# Encoder_Breakout.net
KiCad netlist of a schematic drawn in EAGLE
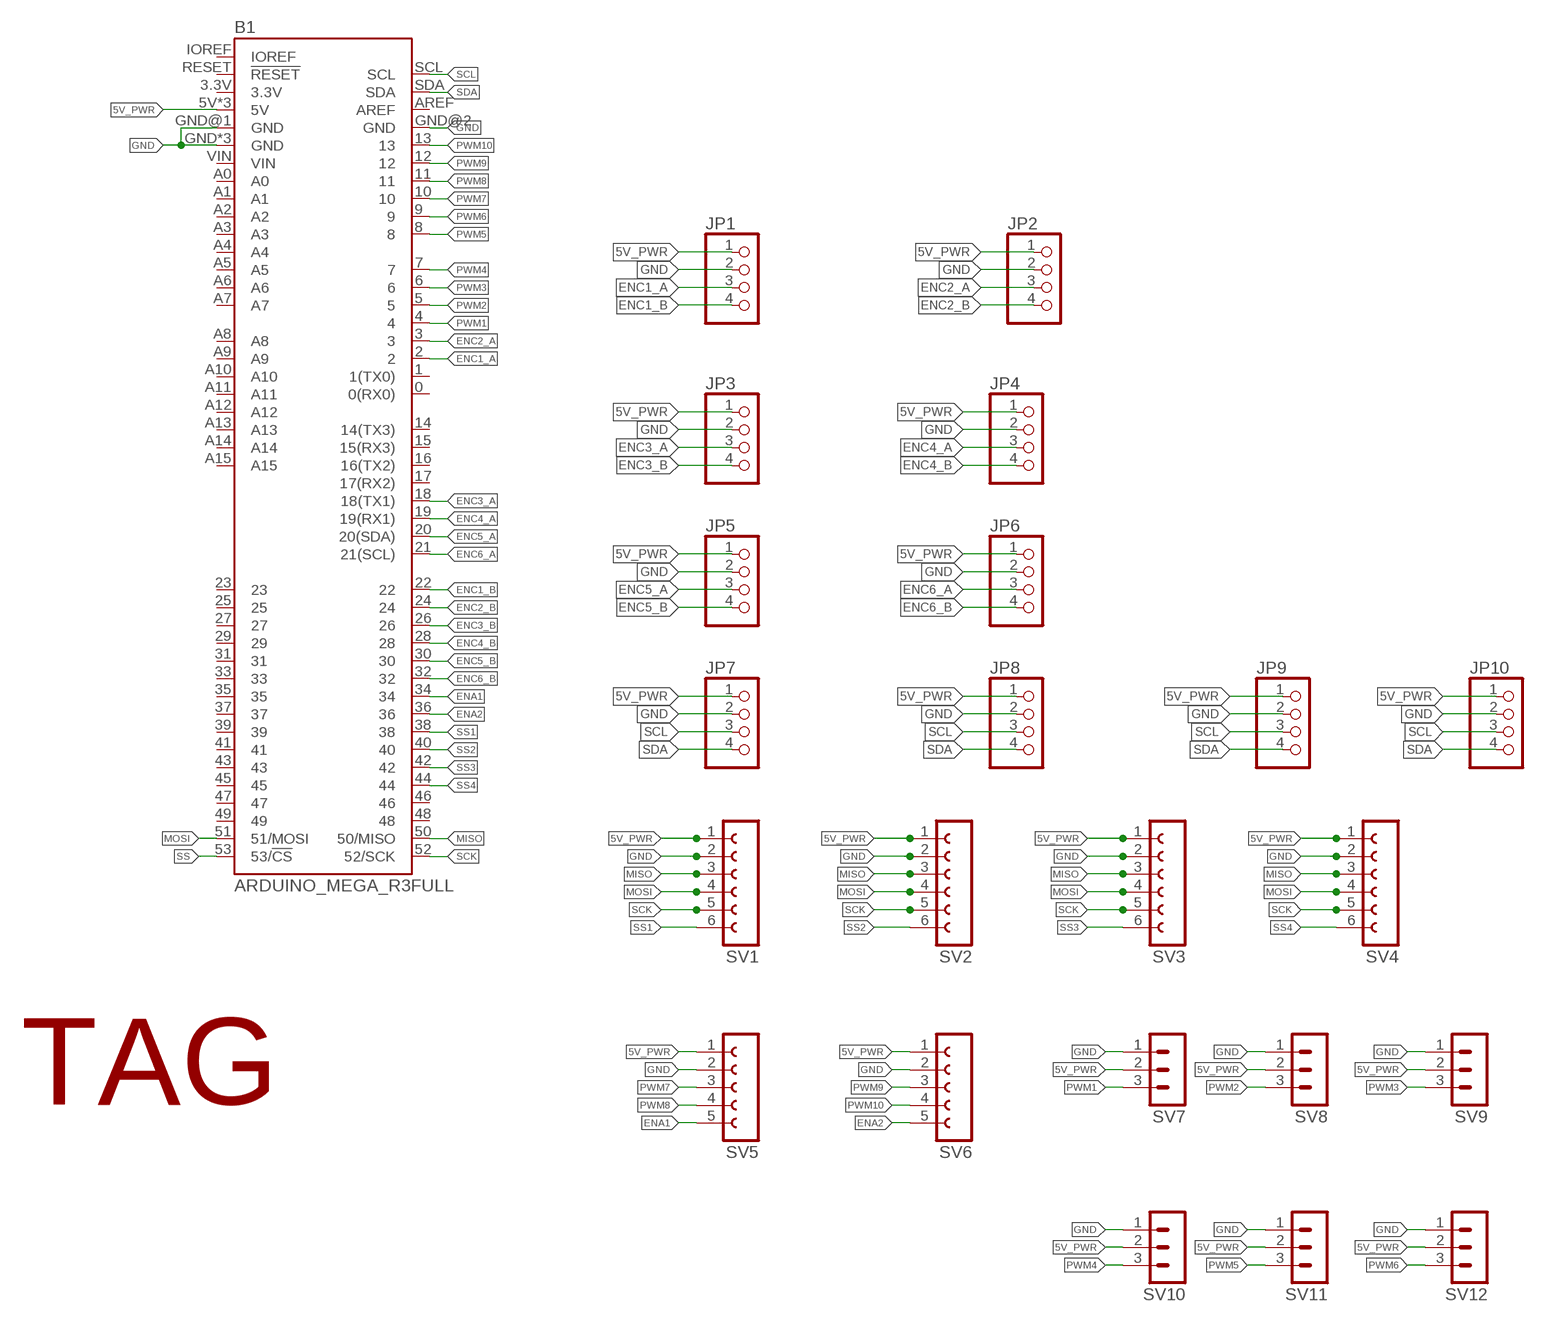
[diagram p0: schematic, sheet 1]

(export (version "E")
  (design (tool "Eeschema 10.0.6"))
  (components
    (comp (ref "B1")
      (value "ARDUINO_MEGA_R3FULL")
      (footprint "eagle-import:ARDUINO_MEGA_NO_SILK")
      (libsource (lib "eagle-import") (part "ARDUINO_MEGA_R3FULL"))
    )
    (comp (ref "JP1")
      (value "PINHD-1X4")
      (footprint "eagle-import:1X04")
      (libsource (lib "eagle-import") (part "PINHD-1X4"))
    )
    (comp (ref "JP2")
      (value "PINHD-1X4")
      (footprint "eagle-import:1X04")
      (libsource (lib "eagle-import") (part "PINHD-1X4"))
    )
    (comp (ref "JP3")
      (value "PINHD-1X4")
      (footprint "eagle-import:1X04")
      (libsource (lib "eagle-import") (part "PINHD-1X4"))
    )
    (comp (ref "JP4")
      (value "PINHD-1X4")
      (footprint "eagle-import:1X04")
      (libsource (lib "eagle-import") (part "PINHD-1X4"))
    )
    (comp (ref "JP5")
      (value "PINHD-1X4")
      (footprint "eagle-import:1X04")
      (libsource (lib "eagle-import") (part "PINHD-1X4"))
    )
    (comp (ref "JP6")
      (value "PINHD-1X4")
      (footprint "eagle-import:1X04")
      (libsource (lib "eagle-import") (part "PINHD-1X4"))
    )
    (comp (ref "JP7")
      (value "PINHD-1X4")
      (footprint "eagle-import:1X04")
      (libsource (lib "eagle-import") (part "PINHD-1X4"))
    )
    (comp (ref "JP8")
      (value "PINHD-1X4")
      (footprint "eagle-import:1X04")
      (libsource (lib "eagle-import") (part "PINHD-1X4"))
    )
    (comp (ref "JP9")
      (value "PINHD-1X4")
      (footprint "eagle-import:1X04")
      (libsource (lib "eagle-import") (part "PINHD-1X4"))
    )
    (comp (ref "JP10")
      (value "PINHD-1X4")
      (footprint "eagle-import:1X04")
      (libsource (lib "eagle-import") (part "PINHD-1X4"))
    )
    (comp (ref "SV1")
      (value "FE06-1")
      (footprint "eagle-import:FE06")
      (libsource (lib "eagle-import") (part "FE06-1"))
    )
    (comp (ref "SV2")
      (value "FE06-1")
      (footprint "eagle-import:FE06")
      (libsource (lib "eagle-import") (part "FE06-1"))
    )
    (comp (ref "SV3")
      (value "FE06-1")
      (footprint "eagle-import:FE06")
      (libsource (lib "eagle-import") (part "FE06-1"))
    )
    (comp (ref "SV4")
      (value "FE06-1")
      (footprint "eagle-import:FE06")
      (libsource (lib "eagle-import") (part "FE06-1"))
    )
    (comp (ref "SV5")
      (value "FE05-1")
      (footprint "eagle-import:FE05-1")
      (libsource (lib "eagle-import") (part "FE05-1"))
    )
    (comp (ref "SV6")
      (value "FE05-1")
      (footprint "eagle-import:FE05-1")
      (libsource (lib "eagle-import") (part "FE05-1"))
    )
    (comp (ref "SV7")
      (value "MA03-1")
      (footprint "eagle-import:MA03-1")
      (libsource (lib "eagle-import") (part "MA03-1"))
    )
    (comp (ref "SV8")
      (value "MA03-1")
      (footprint "eagle-import:MA03-1")
      (libsource (lib "eagle-import") (part "MA03-1"))
    )
    (comp (ref "SV9")
      (value "MA03-1")
      (footprint "eagle-import:MA03-1")
      (libsource (lib "eagle-import") (part "MA03-1"))
    )
    (comp (ref "SV10")
      (value "MA03-1")
      (footprint "eagle-import:MA03-1")
      (libsource (lib "eagle-import") (part "MA03-1"))
    )
    (comp (ref "SV11")
      (value "MA03-1")
      (footprint "eagle-import:MA03-1")
      (libsource (lib "eagle-import") (part "MA03-1"))
    )
    (comp (ref "SV12")
      (value "MA03-1")
      (footprint "eagle-import:MA03-1")
      (libsource (lib "eagle-import") (part "MA03-1"))
    )
    (comp (ref "U$1")
      (value "TAG")
      (footprint "eagle-import:TAG")
      (libsource (lib "eagle-import") (part "TAG"))
    )
  )
  (nets
    (net (code "1") (name "5V_PWR") (class "Default")
      (node (ref "B1") (pin "5V") (pinfunction "5V_5V") (pintype "bidirectional"))
      (node (ref "B1") (pin "5V@1") (pinfunction "5V_5V@1") (pintype "bidirectional"))
      (node (ref "B1") (pin "5V@2") (pinfunction "5V_5V@2") (pintype "bidirectional"))
      (node (ref "JP1") (pin "1") (pinfunction "1_1") (pintype "passive"))
      (node (ref "JP10") (pin "1") (pinfunction "1_1") (pintype "passive"))
      (node (ref "JP2") (pin "1") (pinfunction "1_1") (pintype "passive"))
      (node (ref "JP3") (pin "1") (pinfunction "1_1") (pintype "passive"))
      (node (ref "JP4") (pin "1") (pinfunction "1_1") (pintype "passive"))
      (node (ref "JP5") (pin "1") (pinfunction "1_1") (pintype "passive"))
      (node (ref "JP6") (pin "1") (pinfunction "1_1") (pintype "passive"))
      (node (ref "JP7") (pin "1") (pinfunction "1_1") (pintype "passive"))
      (node (ref "JP8") (pin "1") (pinfunction "1_1") (pintype "passive"))
      (node (ref "JP9") (pin "1") (pinfunction "1_1") (pintype "passive"))
      (node (ref "SV1") (pin "1") (pinfunction "1_1") (pintype "passive"))
      (node (ref "SV10") (pin "2") (pinfunction "2_2") (pintype "passive"))
      (node (ref "SV11") (pin "2") (pinfunction "2_2") (pintype "passive"))
      (node (ref "SV12") (pin "2") (pinfunction "2_2") (pintype "passive"))
      (node (ref "SV2") (pin "1") (pinfunction "1_1") (pintype "passive"))
      (node (ref "SV3") (pin "1") (pinfunction "1_1") (pintype "passive"))
      (node (ref "SV4") (pin "1") (pinfunction "1_1") (pintype "passive"))
      (node (ref "SV5") (pin "1") (pinfunction "1_1") (pintype "passive"))
      (node (ref "SV6") (pin "1") (pinfunction "1_1") (pintype "passive"))
      (node (ref "SV7") (pin "2") (pinfunction "2_2") (pintype "passive"))
      (node (ref "SV8") (pin "2") (pinfunction "2_2") (pintype "passive"))
      (node (ref "SV9") (pin "2") (pinfunction "2_2") (pintype "passive"))
    )
    (net (code "2") (name "ENA1") (class "Default")
      (node (ref "B1") (pin "34") (pinfunction "34_34") (pintype "bidirectional"))
      (node (ref "SV5") (pin "5") (pinfunction "5_5") (pintype "passive"))
    )
    (net (code "3") (name "ENA2") (class "Default")
      (node (ref "B1") (pin "36") (pinfunction "36_36") (pintype "bidirectional"))
      (node (ref "SV6") (pin "5") (pinfunction "5_5") (pintype "passive"))
    )
    (net (code "4") (name "ENC1_A") (class "Default")
      (node (ref "B1") (pin "2") (pinfunction "2_2") (pintype "bidirectional"))
      (node (ref "JP1") (pin "3") (pinfunction "3_3") (pintype "passive"))
    )
    (net (code "5") (name "ENC1_B") (class "Default")
      (node (ref "B1") (pin "22") (pinfunction "22_22") (pintype "bidirectional"))
      (node (ref "JP1") (pin "4") (pinfunction "4_4") (pintype "passive"))
    )
    (net (code "6") (name "ENC2_A") (class "Default")
      (node (ref "B1") (pin "3") (pinfunction "3_3") (pintype "bidirectional"))
      (node (ref "JP2") (pin "3") (pinfunction "3_3") (pintype "passive"))
    )
    (net (code "7") (name "ENC2_B") (class "Default")
      (node (ref "B1") (pin "24") (pinfunction "24_24") (pintype "bidirectional"))
      (node (ref "JP2") (pin "4") (pinfunction "4_4") (pintype "passive"))
    )
    (net (code "8") (name "ENC3_A") (class "Default")
      (node (ref "B1") (pin "18") (pinfunction "18(TX1)_18") (pintype "bidirectional"))
      (node (ref "JP3") (pin "3") (pinfunction "3_3") (pintype "passive"))
    )
    (net (code "9") (name "ENC3_B") (class "Default")
      (node (ref "B1") (pin "26") (pinfunction "26_26") (pintype "bidirectional"))
      (node (ref "JP3") (pin "4") (pinfunction "4_4") (pintype "passive"))
    )
    (net (code "10") (name "ENC4_A") (class "Default")
      (node (ref "B1") (pin "19") (pinfunction "19(RX1)_19") (pintype "bidirectional"))
      (node (ref "JP4") (pin "3") (pinfunction "3_3") (pintype "passive"))
    )
    (net (code "11") (name "ENC4_B") (class "Default")
      (node (ref "B1") (pin "28") (pinfunction "28_28") (pintype "bidirectional"))
      (node (ref "JP4") (pin "4") (pinfunction "4_4") (pintype "passive"))
    )
    (net (code "12") (name "ENC5_A") (class "Default")
      (node (ref "B1") (pin "20") (pinfunction "20(SDA)_20") (pintype "bidirectional"))
      (node (ref "JP5") (pin "3") (pinfunction "3_3") (pintype "passive"))
    )
    (net (code "13") (name "ENC5_B") (class "Default")
      (node (ref "B1") (pin "30") (pinfunction "30_30") (pintype "bidirectional"))
      (node (ref "JP5") (pin "4") (pinfunction "4_4") (pintype "passive"))
    )
    (net (code "14") (name "ENC6_A") (class "Default")
      (node (ref "B1") (pin "21") (pinfunction "21(SCL)_21") (pintype "bidirectional"))
      (node (ref "JP6") (pin "3") (pinfunction "3_3") (pintype "passive"))
    )
    (net (code "15") (name "ENC6_B") (class "Default")
      (node (ref "B1") (pin "32") (pinfunction "32_32") (pintype "bidirectional"))
      (node (ref "JP6") (pin "4") (pinfunction "4_4") (pintype "passive"))
    )
    (net (code "16") (name "GND") (class "Default")
      (node (ref "B1") (pin "GND") (pinfunction "GND_GND") (pintype "bidirectional"))
      (node (ref "B1") (pin "GND@1") (pinfunction "GND_GND@1") (pintype "bidirectional"))
      (node (ref "B1") (pin "GND@2") (pinfunction "GND_GND@2") (pintype "bidirectional"))
      (node (ref "B1") (pin "GND@3") (pinfunction "GND_GND@3") (pintype "bidirectional"))
      (node (ref "B1") (pin "GND@4") (pinfunction "GND_GND@4") (pintype "bidirectional"))
      (node (ref "JP1") (pin "2") (pinfunction "2_2") (pintype "passive"))
      (node (ref "JP10") (pin "2") (pinfunction "2_2") (pintype "passive"))
      (node (ref "JP2") (pin "2") (pinfunction "2_2") (pintype "passive"))
      (node (ref "JP3") (pin "2") (pinfunction "2_2") (pintype "passive"))
      (node (ref "JP4") (pin "2") (pinfunction "2_2") (pintype "passive"))
      (node (ref "JP5") (pin "2") (pinfunction "2_2") (pintype "passive"))
      (node (ref "JP6") (pin "2") (pinfunction "2_2") (pintype "passive"))
      (node (ref "JP7") (pin "2") (pinfunction "2_2") (pintype "passive"))
      (node (ref "JP8") (pin "2") (pinfunction "2_2") (pintype "passive"))
      (node (ref "JP9") (pin "2") (pinfunction "2_2") (pintype "passive"))
      (node (ref "SV1") (pin "2") (pinfunction "2_2") (pintype "passive"))
      (node (ref "SV10") (pin "1") (pinfunction "1_1") (pintype "passive"))
      (node (ref "SV11") (pin "1") (pinfunction "1_1") (pintype "passive"))
      (node (ref "SV12") (pin "1") (pinfunction "1_1") (pintype "passive"))
      (node (ref "SV2") (pin "2") (pinfunction "2_2") (pintype "passive"))
      (node (ref "SV3") (pin "2") (pinfunction "2_2") (pintype "passive"))
      (node (ref "SV4") (pin "2") (pinfunction "2_2") (pintype "passive"))
      (node (ref "SV5") (pin "2") (pinfunction "2_2") (pintype "passive"))
      (node (ref "SV6") (pin "2") (pinfunction "2_2") (pintype "passive"))
      (node (ref "SV7") (pin "1") (pinfunction "1_1") (pintype "passive"))
      (node (ref "SV8") (pin "1") (pinfunction "1_1") (pintype "passive"))
      (node (ref "SV9") (pin "1") (pinfunction "1_1") (pintype "passive"))
    )
    (net (code "17") (name "MISO") (class "Default")
      (node (ref "B1") (pin "50") (pinfunction "50/MISO_50") (pintype "bidirectional"))
      (node (ref "SV1") (pin "3") (pinfunction "3_3") (pintype "passive"))
      (node (ref "SV2") (pin "3") (pinfunction "3_3") (pintype "passive"))
      (node (ref "SV3") (pin "3") (pinfunction "3_3") (pintype "passive"))
      (node (ref "SV4") (pin "3") (pinfunction "3_3") (pintype "passive"))
    )
    (net (code "18") (name "MOSI") (class "Default")
      (node (ref "B1") (pin "51") (pinfunction "51/MOSI_51") (pintype "bidirectional"))
      (node (ref "SV1") (pin "4") (pinfunction "4_4") (pintype "passive"))
      (node (ref "SV2") (pin "4") (pinfunction "4_4") (pintype "passive"))
      (node (ref "SV3") (pin "4") (pinfunction "4_4") (pintype "passive"))
      (node (ref "SV4") (pin "4") (pinfunction "4_4") (pintype "passive"))
    )
    (net (code "19") (name "PWM1") (class "Default")
      (node (ref "B1") (pin "4") (pinfunction "4_4") (pintype "bidirectional"))
      (node (ref "SV7") (pin "3") (pinfunction "3_3") (pintype "passive"))
    )
    (net (code "20") (name "PWM2") (class "Default")
      (node (ref "B1") (pin "5") (pinfunction "5_5") (pintype "bidirectional"))
      (node (ref "SV8") (pin "3") (pinfunction "3_3") (pintype "passive"))
    )
    (net (code "21") (name "PWM3") (class "Default")
      (node (ref "B1") (pin "6") (pinfunction "6_6") (pintype "bidirectional"))
      (node (ref "SV9") (pin "3") (pinfunction "3_3") (pintype "passive"))
    )
    (net (code "22") (name "PWM4") (class "Default")
      (node (ref "B1") (pin "7") (pinfunction "7_7") (pintype "bidirectional"))
      (node (ref "SV10") (pin "3") (pinfunction "3_3") (pintype "passive"))
    )
    (net (code "23") (name "PWM5") (class "Default")
      (node (ref "B1") (pin "8") (pinfunction "8_8") (pintype "bidirectional"))
      (node (ref "SV11") (pin "3") (pinfunction "3_3") (pintype "passive"))
    )
    (net (code "24") (name "PWM6") (class "Default")
      (node (ref "B1") (pin "9") (pinfunction "9_9") (pintype "bidirectional"))
      (node (ref "SV12") (pin "3") (pinfunction "3_3") (pintype "passive"))
    )
    (net (code "25") (name "PWM7") (class "Default")
      (node (ref "B1") (pin "10") (pinfunction "10_10") (pintype "bidirectional"))
      (node (ref "SV5") (pin "3") (pinfunction "3_3") (pintype "passive"))
    )
    (net (code "26") (name "PWM8") (class "Default")
      (node (ref "B1") (pin "11") (pinfunction "11_11") (pintype "bidirectional"))
      (node (ref "SV5") (pin "4") (pinfunction "4_4") (pintype "passive"))
    )
    (net (code "27") (name "PWM9") (class "Default")
      (node (ref "B1") (pin "12") (pinfunction "12_12") (pintype "bidirectional"))
      (node (ref "SV6") (pin "3") (pinfunction "3_3") (pintype "passive"))
    )
    (net (code "28") (name "PWM10") (class "Default")
      (node (ref "B1") (pin "13") (pinfunction "13_13") (pintype "bidirectional"))
      (node (ref "SV6") (pin "4") (pinfunction "4_4") (pintype "passive"))
    )
    (net (code "29") (name "SCK") (class "Default")
      (node (ref "B1") (pin "52") (pinfunction "52/SCK_52") (pintype "bidirectional"))
      (node (ref "SV1") (pin "5") (pinfunction "5_5") (pintype "passive"))
      (node (ref "SV2") (pin "5") (pinfunction "5_5") (pintype "passive"))
      (node (ref "SV3") (pin "5") (pinfunction "5_5") (pintype "passive"))
      (node (ref "SV4") (pin "5") (pinfunction "5_5") (pintype "passive"))
    )
    (net (code "30") (name "SCL") (class "Default")
      (node (ref "B1") (pin "SCL") (pinfunction "SCL_SCL") (pintype "bidirectional"))
      (node (ref "JP10") (pin "3") (pinfunction "3_3") (pintype "passive"))
      (node (ref "JP7") (pin "3") (pinfunction "3_3") (pintype "passive"))
      (node (ref "JP8") (pin "3") (pinfunction "3_3") (pintype "passive"))
      (node (ref "JP9") (pin "3") (pinfunction "3_3") (pintype "passive"))
    )
    (net (code "31") (name "SDA") (class "Default")
      (node (ref "B1") (pin "SDA") (pinfunction "SDA_SDA") (pintype "bidirectional"))
      (node (ref "JP10") (pin "4") (pinfunction "4_4") (pintype "passive"))
      (node (ref "JP7") (pin "4") (pinfunction "4_4") (pintype "passive"))
      (node (ref "JP8") (pin "4") (pinfunction "4_4") (pintype "passive"))
      (node (ref "JP9") (pin "4") (pinfunction "4_4") (pintype "passive"))
    )
    (net (code "32") (name "SS") (class "Default")
      (node (ref "B1") (pin "53") (pinfunction "53/~{CS}_53") (pintype "bidirectional"))
    )
    (net (code "33") (name "SS1") (class "Default")
      (node (ref "B1") (pin "38") (pinfunction "38_38") (pintype "bidirectional"))
      (node (ref "SV1") (pin "6") (pinfunction "6_6") (pintype "passive"))
    )
    (net (code "34") (name "SS2") (class "Default")
      (node (ref "B1") (pin "40") (pinfunction "40_40") (pintype "bidirectional"))
      (node (ref "SV2") (pin "6") (pinfunction "6_6") (pintype "passive"))
    )
    (net (code "35") (name "SS3") (class "Default")
      (node (ref "B1") (pin "42") (pinfunction "42_42") (pintype "bidirectional"))
      (node (ref "SV3") (pin "6") (pinfunction "6_6") (pintype "passive"))
    )
    (net (code "36") (name "SS4") (class "Default")
      (node (ref "B1") (pin "44") (pinfunction "44_44") (pintype "bidirectional"))
      (node (ref "SV4") (pin "6") (pinfunction "6_6") (pintype "passive"))
    )
    (net (code "37") (name "unconnected-(B1-0(RX0)-Pad0)") (class "Default")
      (node (ref "B1") (pin "0") (pinfunction "0(RX0)_0") (pintype "bidirectional"))
    )
    (net (code "38") (name "unconnected-(B1-1(TX0)-Pad1)") (class "Default")
      (node (ref "B1") (pin "1") (pinfunction "1(TX0)_1") (pintype "bidirectional"))
    )
    (net (code "39") (name "unconnected-(B1-14(TX3)-Pad14)") (class "Default")
      (node (ref "B1") (pin "14") (pinfunction "14(TX3)_14") (pintype "bidirectional"))
    )
    (net (code "40") (name "unconnected-(B1-15(RX3)-Pad15)") (class "Default")
      (node (ref "B1") (pin "15") (pinfunction "15(RX3)_15") (pintype "bidirectional"))
    )
    (net (code "41") (name "unconnected-(B1-16(TX2)-Pad16)") (class "Default")
      (node (ref "B1") (pin "16") (pinfunction "16(TX2)_16") (pintype "bidirectional"))
    )
    (net (code "42") (name "unconnected-(B1-17(RX2)-Pad17)") (class "Default")
      (node (ref "B1") (pin "17") (pinfunction "17(RX2)_17") (pintype "bidirectional"))
    )
    (net (code "43") (name "unconnected-(B1-Pad3.3V)") (class "Default")
      (node (ref "B1") (pin "3.3V") (pinfunction "3.3V_3.3V") (pintype "bidirectional"))
    )
    (net (code "44") (name "unconnected-(B1-Pad23)") (class "Default")
      (node (ref "B1") (pin "23") (pinfunction "23_23") (pintype "bidirectional"))
    )
    (net (code "45") (name "unconnected-(B1-Pad25)") (class "Default")
      (node (ref "B1") (pin "25") (pinfunction "25_25") (pintype "bidirectional"))
    )
    (net (code "46") (name "unconnected-(B1-Pad27)") (class "Default")
      (node (ref "B1") (pin "27") (pinfunction "27_27") (pintype "bidirectional"))
    )
    (net (code "47") (name "unconnected-(B1-Pad29)") (class "Default")
      (node (ref "B1") (pin "29") (pinfunction "29_29") (pintype "bidirectional"))
    )
    (net (code "48") (name "unconnected-(B1-Pad31)") (class "Default")
      (node (ref "B1") (pin "31") (pinfunction "31_31") (pintype "bidirectional"))
    )
    (net (code "49") (name "unconnected-(B1-Pad33)") (class "Default")
      (node (ref "B1") (pin "33") (pinfunction "33_33") (pintype "bidirectional"))
    )
    (net (code "50") (name "unconnected-(B1-Pad35)") (class "Default")
      (node (ref "B1") (pin "35") (pinfunction "35_35") (pintype "bidirectional"))
    )
    (net (code "51") (name "unconnected-(B1-Pad37)") (class "Default")
      (node (ref "B1") (pin "37") (pinfunction "37_37") (pintype "bidirectional"))
    )
    (net (code "52") (name "unconnected-(B1-Pad39)") (class "Default")
      (node (ref "B1") (pin "39") (pinfunction "39_39") (pintype "bidirectional"))
    )
    (net (code "53") (name "unconnected-(B1-Pad41)") (class "Default")
      (node (ref "B1") (pin "41") (pinfunction "41_41") (pintype "bidirectional"))
    )
    (net (code "54") (name "unconnected-(B1-Pad43)") (class "Default")
      (node (ref "B1") (pin "43") (pinfunction "43_43") (pintype "bidirectional"))
    )
    (net (code "55") (name "unconnected-(B1-Pad45)") (class "Default")
      (node (ref "B1") (pin "45") (pinfunction "45_45") (pintype "bidirectional"))
    )
    (net (code "56") (name "unconnected-(B1-Pad46)") (class "Default")
      (node (ref "B1") (pin "46") (pinfunction "46_46") (pintype "bidirectional"))
    )
    (net (code "57") (name "unconnected-(B1-Pad47)") (class "Default")
      (node (ref "B1") (pin "47") (pinfunction "47_47") (pintype "bidirectional"))
    )
    (net (code "58") (name "unconnected-(B1-Pad48)") (class "Default")
      (node (ref "B1") (pin "48") (pinfunction "48_48") (pintype "bidirectional"))
    )
    (net (code "59") (name "unconnected-(B1-Pad49)") (class "Default")
      (node (ref "B1") (pin "49") (pinfunction "49_49") (pintype "bidirectional"))
    )
    (net (code "60") (name "unconnected-(B1-PadA0)") (class "Default")
      (node (ref "B1") (pin "A0") (pinfunction "A0_A0") (pintype "bidirectional"))
    )
    (net (code "61") (name "unconnected-(B1-PadA1)") (class "Default")
      (node (ref "B1") (pin "A1") (pinfunction "A1_A1") (pintype "bidirectional"))
    )
    (net (code "62") (name "unconnected-(B1-PadA2)") (class "Default")
      (node (ref "B1") (pin "A2") (pinfunction "A2_A2") (pintype "bidirectional"))
    )
    (net (code "63") (name "unconnected-(B1-PadA3)") (class "Default")
      (node (ref "B1") (pin "A3") (pinfunction "A3_A3") (pintype "bidirectional"))
    )
    (net (code "64") (name "unconnected-(B1-PadA4)") (class "Default")
      (node (ref "B1") (pin "A4") (pinfunction "A4_A4") (pintype "bidirectional"))
    )
    (net (code "65") (name "unconnected-(B1-PadA5)") (class "Default")
      (node (ref "B1") (pin "A5") (pinfunction "A5_A5") (pintype "bidirectional"))
    )
    (net (code "66") (name "unconnected-(B1-PadA6)") (class "Default")
      (node (ref "B1") (pin "A6") (pinfunction "A6_A6") (pintype "bidirectional"))
    )
    (net (code "67") (name "unconnected-(B1-PadA7)") (class "Default")
      (node (ref "B1") (pin "A7") (pinfunction "A7_A7") (pintype "bidirectional"))
    )
    (net (code "68") (name "unconnected-(B1-PadA8)") (class "Default")
      (node (ref "B1") (pin "A8") (pinfunction "A8_A8") (pintype "bidirectional"))
    )
    (net (code "69") (name "unconnected-(B1-PadA9)") (class "Default")
      (node (ref "B1") (pin "A9") (pinfunction "A9_A9") (pintype "bidirectional"))
    )
    (net (code "70") (name "unconnected-(B1-PadA10)") (class "Default")
      (node (ref "B1") (pin "A10") (pinfunction "A10_A10") (pintype "bidirectional"))
    )
    (net (code "71") (name "unconnected-(B1-PadA11)") (class "Default")
      (node (ref "B1") (pin "A11") (pinfunction "A11_A11") (pintype "bidirectional"))
    )
    (net (code "72") (name "unconnected-(B1-PadA12)") (class "Default")
      (node (ref "B1") (pin "A12") (pinfunction "A12_A12") (pintype "bidirectional"))
    )
    (net (code "73") (name "unconnected-(B1-PadA13)") (class "Default")
      (node (ref "B1") (pin "A13") (pinfunction "A13_A13") (pintype "bidirectional"))
    )
    (net (code "74") (name "unconnected-(B1-PadA14)") (class "Default")
      (node (ref "B1") (pin "A14") (pinfunction "A14_A14") (pintype "bidirectional"))
    )
    (net (code "75") (name "unconnected-(B1-PadA15)") (class "Default")
      (node (ref "B1") (pin "A15") (pinfunction "A15_A15") (pintype "bidirectional"))
    )
    (net (code "76") (name "unconnected-(B1-PadAREF)") (class "Default")
      (node (ref "B1") (pin "AREF") (pinfunction "AREF_AREF") (pintype "bidirectional"))
    )
    (net (code "77") (name "unconnected-(B1-PadIOREF)") (class "Default")
      (node (ref "B1") (pin "IOREF") (pinfunction "IOREF_IOREF") (pintype "bidirectional"))
    )
    (net (code "78") (name "unconnected-(B1-PadVIN)") (class "Default")
      (node (ref "B1") (pin "VIN") (pinfunction "VIN_VIN") (pintype "bidirectional"))
    )
    (net (code "79") (name "unconnected-(B1-~{RESET}-PadRESET)") (class "Default")
      (node (ref "B1") (pin "RESET") (pinfunction "~{RESET}_RESET") (pintype "bidirectional"))
    )
  )
)
